# assignment1.net
KiCad netlist of a schematic drawn in EAGLE
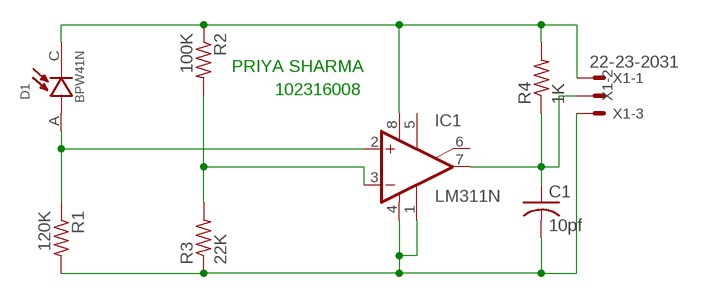
[diagram p0: schematic, sheet 1]

(export (version "E")
  (design (tool "Eeschema 10.0.6"))
  (components
    (comp (ref "C1")
      (value "10pf")
      (footprint "eagle-import:C025-024X044")
      (libsource (lib "eagle-import") (part "C-US025-024X044"))
    )
    (comp (ref "D1")
      (value "BPW41N")
      (footprint "eagle-import:DIO_BPW41N")
      (fields (field (name "MF") "Vishay Semiconductor Opto Division"))
      (libsource (lib "eagle-import") (part "BPW41N"))
    )
    (comp (ref "IC1")
      (value "LM311N")
      (footprint "eagle-import:DIL08")
      (libsource (lib "eagle-import") (part "LM311N"))
    )
    (comp (ref "R1")
      (value "120K")
      (footprint "eagle-import:0204_5")
      (libsource (lib "eagle-import") (part "R-US_0204/5"))
    )
    (comp (ref "R2")
      (value "100K")
      (footprint "eagle-import:0204_5")
      (libsource (lib "eagle-import") (part "R-US_0204/5"))
    )
    (comp (ref "R3")
      (value "22K")
      (footprint "eagle-import:0204_5")
      (libsource (lib "eagle-import") (part "R-US_0204/5"))
    )
    (comp (ref "R4")
      (value "1K")
      (footprint "eagle-import:0204_5")
      (libsource (lib "eagle-import") (part "R-US_0204/5"))
    )
    (comp (ref "X1")
      (value "22-23-2031")
      (footprint "eagle-import:22-23-2031")
      (fields (field (name "MF") "MOLEX"))
      (libsource (lib "eagle-import") (part "22-23-2031"))
    )
  )
  (nets
    (net (code "1") (name "Net-(IC1-+IN)") (class "Default")
      (node (ref "D1") (pin "A") (pinfunction "A_A") (pintype "passive"))
      (node (ref "IC1") (pin "2") (pinfunction "+IN_2") (pintype "input"))
      (node (ref "R1") (pin "1") (pinfunction "1_1") (pintype "passive"))
    )
    (net (code "2") (name "Net-(IC1--IN)") (class "Default")
      (node (ref "IC1") (pin "3") (pinfunction "-IN_3") (pintype "input"))
      (node (ref "R2") (pin "2") (pinfunction "2_2") (pintype "passive"))
      (node (ref "R3") (pin "2") (pinfunction "2_2") (pintype "passive"))
    )
    (net (code "3") (name "Net-(IC1-GND)") (class "Default")
      (node (ref "C1") (pin "2") (pinfunction "2_2") (pintype "passive"))
      (node (ref "IC1") (pin "1") (pinfunction "GND_1") (pintype "passive"))
      (node (ref "IC1") (pin "4") (pinfunction "V-_4") (pintype "power_in"))
      (node (ref "R1") (pin "2") (pinfunction "2_2") (pintype "passive"))
      (node (ref "R3") (pin "1") (pinfunction "1_1") (pintype "passive"))
      (node (ref "X1") (pin "3") (pinfunction "S_3") (pintype "passive"))
    )
    (net (code "4") (name "Net-(IC1-OUT)") (class "Default")
      (node (ref "C1") (pin "1") (pinfunction "1_1") (pintype "passive"))
      (node (ref "IC1") (pin "7") (pinfunction "OUT_7") (pintype "output"))
      (node (ref "R4") (pin "1") (pinfunction "1_1") (pintype "passive"))
      (node (ref "X1") (pin "2") (pinfunction "S_2") (pintype "passive"))
    )
    (net (code "5") (name "Net-(IC1-V+)") (class "Default")
      (node (ref "D1") (pin "C") (pinfunction "C_C") (pintype "passive"))
      (node (ref "IC1") (pin "8") (pinfunction "V+_8") (pintype "power_in"))
      (node (ref "R2") (pin "1") (pinfunction "1_1") (pintype "passive"))
      (node (ref "R4") (pin "2") (pinfunction "2_2") (pintype "passive"))
      (node (ref "X1") (pin "1") (pinfunction "S_1") (pintype "passive"))
    )
    (net (code "6") (name "unconnected-(IC1-ON-Pad5)") (class "Default")
      (node (ref "IC1") (pin "5") (pinfunction "ON_5") (pintype "passive"))
    )
    (net (code "7") (name "unconnected-(IC1-ON{slash}STR-Pad6)") (class "Default")
      (node (ref "IC1") (pin "6") (pinfunction "ON/STR_6") (pintype "passive"))
    )
  )
)
